# RF_Front.net
KiCad netlist of a schematic drawn in Altium Designer
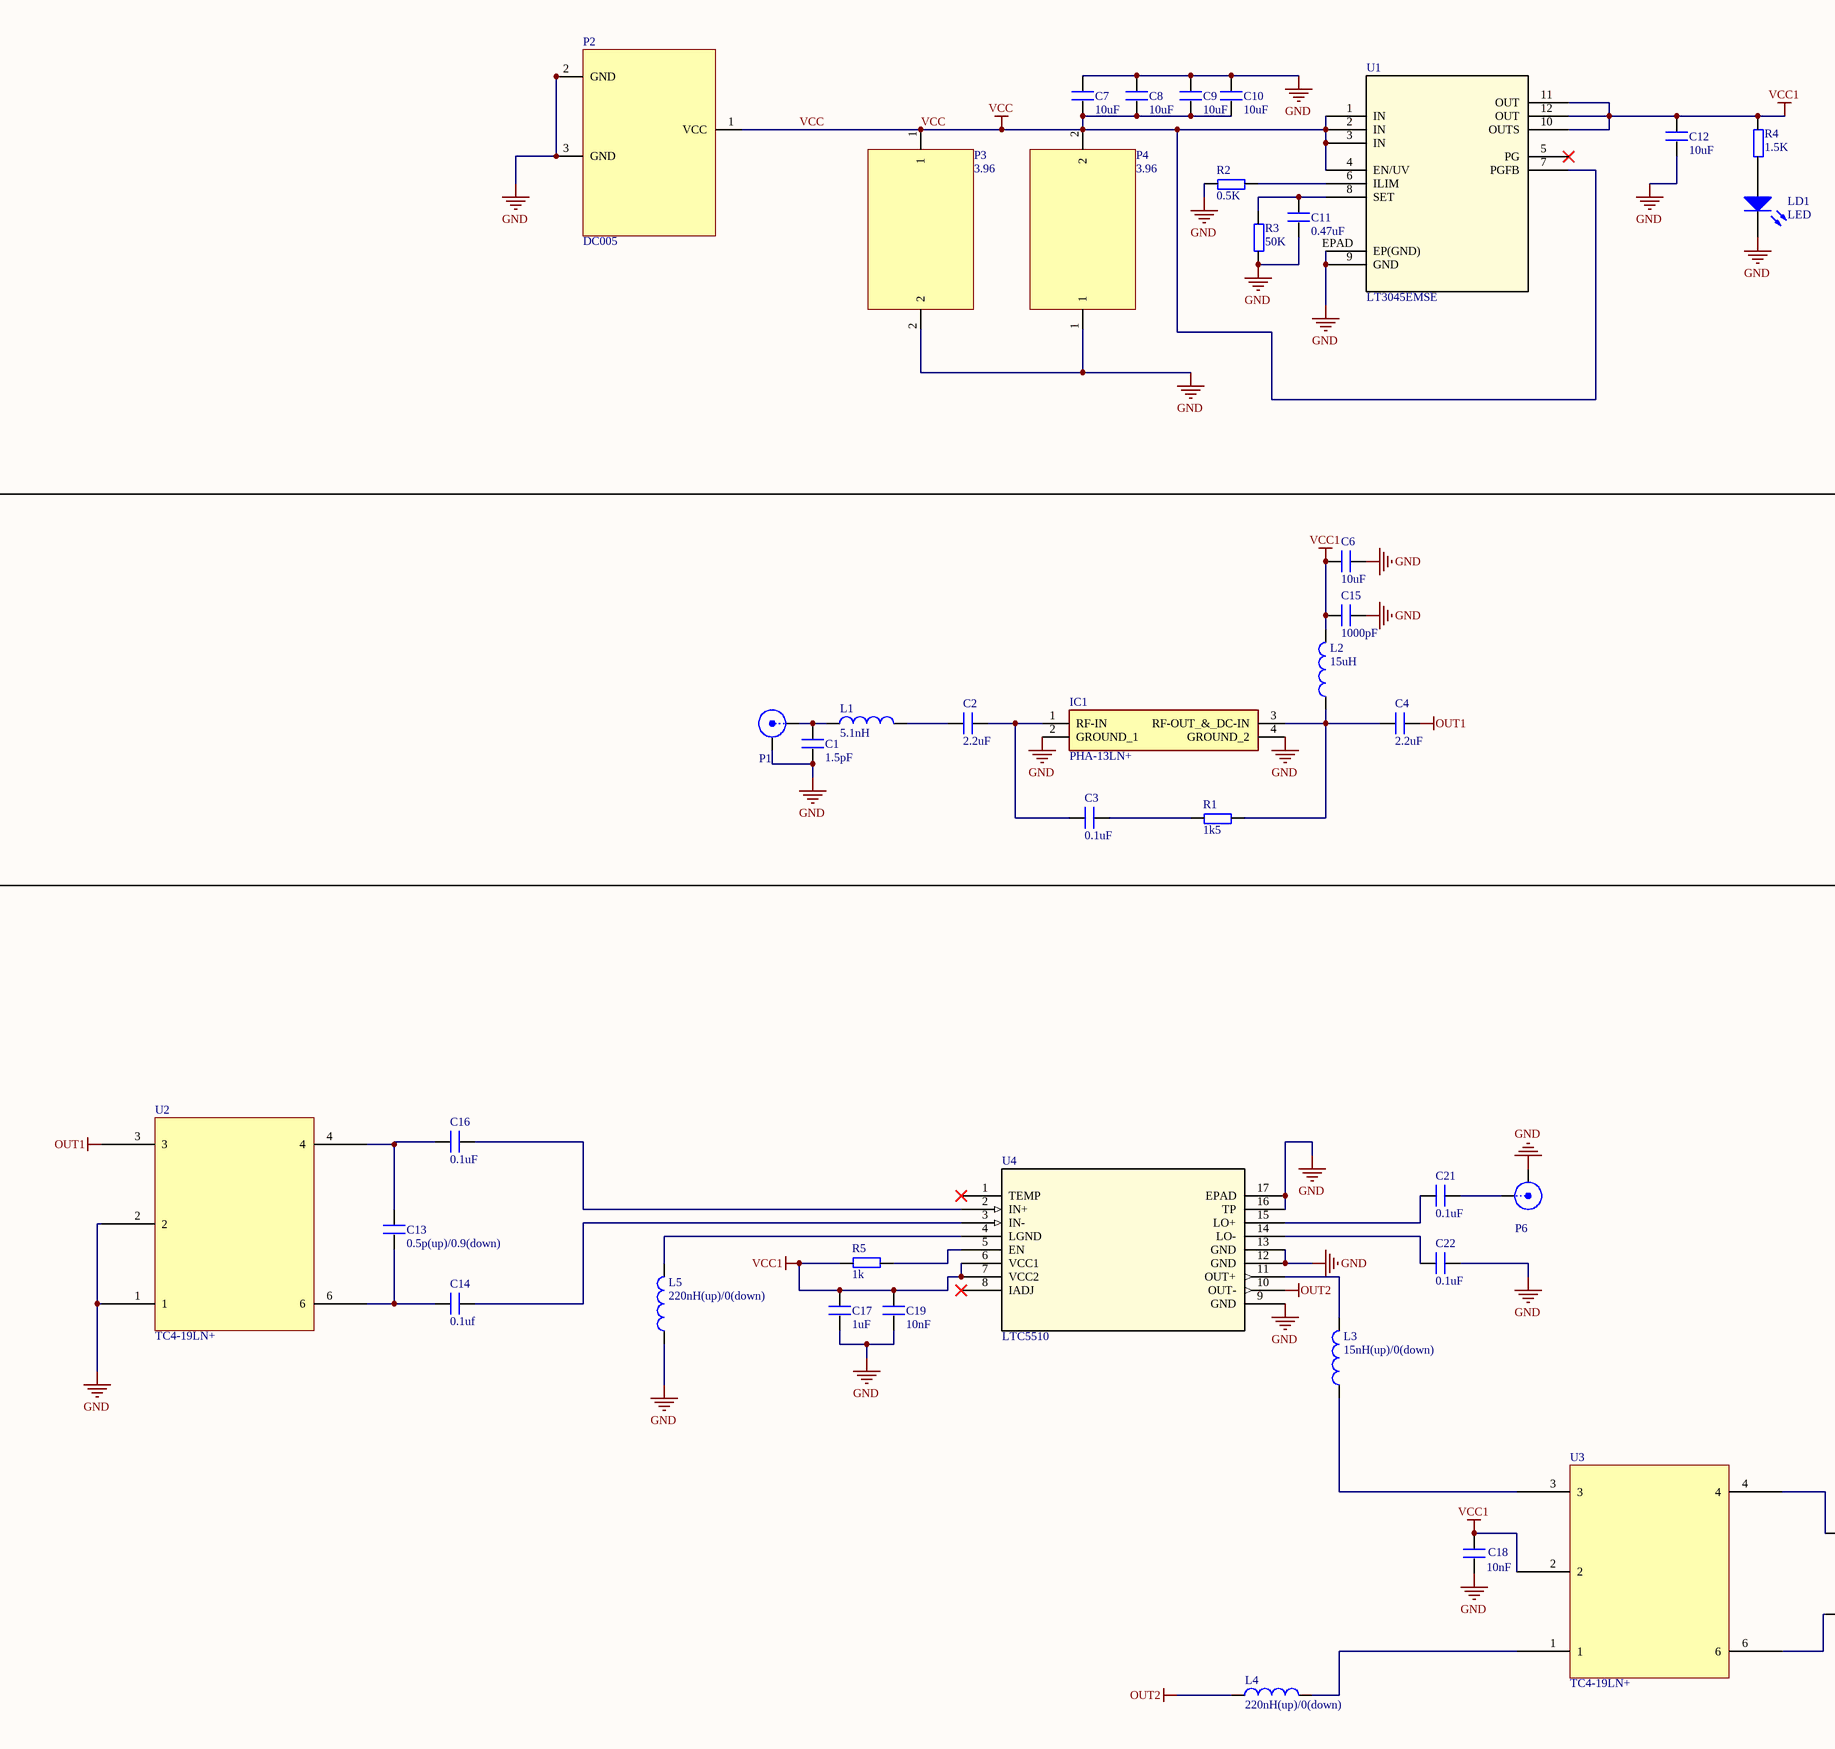
[diagram p0: RF Front.SchDoc, left]
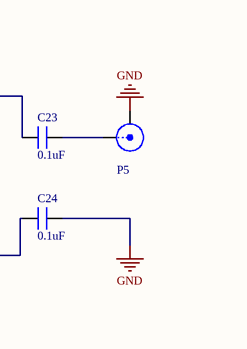
[diagram p1: RF Front.SchDoc, right]

(export (version "E")
  (design (tool "Eeschema 10.0.6"))
  (components
    (comp (ref "C1")
      (value "1.5pF")
      (footprint "0402")
      (description "Capacitor")
      (libsource (lib "MYLIB") (part "C"))
    )
    (comp (ref "C2")
      (value "2.2uF")
      (footprint "0402")
      (description "Capacitor")
      (libsource (lib "MYLIB") (part "C"))
    )
    (comp (ref "C3")
      (value "0.1uF")
      (footprint "0402")
      (description "Capacitor")
      (libsource (lib "MYLIB") (part "C"))
    )
    (comp (ref "C4")
      (value "2.2uF")
      (footprint "0402")
      (description "Capacitor")
      (libsource (lib "MYLIB") (part "C"))
    )
    (comp (ref "C6")
      (value "10uF")
      (footprint "0603C")
      (description "Capacitor")
      (libsource (lib "MYLIB") (part "C"))
    )
    (comp (ref "C7")
      (value "10uF")
      (footprint "CAP 1.5*4*8")
      (description "Capacitor")
      (libsource (lib "MYLIB") (part "C"))
    )
    (comp (ref "C8")
      (value "10uF")
      (footprint "CAP 1.5*4*8")
      (description "Capacitor")
      (libsource (lib "MYLIB") (part "C"))
    )
    (comp (ref "C9")
      (value "10uF")
      (footprint "0603C")
      (description "Capacitor")
      (libsource (lib "MYLIB") (part "C"))
    )
    (comp (ref "C10")
      (value "10uF")
      (footprint "0603C")
      (description "Capacitor")
      (libsource (lib "MYLIB") (part "C"))
    )
    (comp (ref "C11")
      (value "0.47uF")
      (footprint "0402")
      (description "Capacitor")
      (libsource (lib "MYLIB") (part "C"))
    )
    (comp (ref "C12")
      (value "10uF")
      (footprint "0402")
      (description "Capacitor")
      (libsource (lib "MYLIB") (part "C"))
    )
    (comp (ref "C13")
      (value "0.5p(up)/0.9(down)")
      (footprint "0402")
      (description "Capacitor")
      (libsource (lib "MYLIB") (part "C"))
    )
    (comp (ref "C14")
      (value "0.1uf")
      (footprint "0402")
      (description "Capacitor")
      (libsource (lib "MYLIB") (part "C"))
    )
    (comp (ref "C15")
      (value "1000pF")
      (footprint "0402")
      (description "Capacitor")
      (libsource (lib "MYLIB") (part "C"))
    )
    (comp (ref "C16")
      (value "0.1uF")
      (footprint "0402")
      (description "Capacitor")
      (libsource (lib "MYLIB") (part "C"))
    )
    (comp (ref "C17")
      (value "1uF")
      (footprint "0402")
      (description "Capacitor")
      (libsource (lib "MYLIB") (part "C"))
    )
    (comp (ref "C18")
      (value "10nF")
      (footprint "0402")
      (description "Capacitor")
      (libsource (lib "MYLIB") (part "C"))
    )
    (comp (ref "C19")
      (value "10nF")
      (footprint "0402")
      (description "Capacitor")
      (libsource (lib "MYLIB") (part "C"))
    )
    (comp (ref "C21")
      (value "0.1uF")
      (footprint "0402")
      (description "Capacitor")
      (libsource (lib "MYLIB") (part "C"))
    )
    (comp (ref "C22")
      (value "0.1uF")
      (footprint "0402")
      (description "Capacitor")
      (libsource (lib "MYLIB") (part "C"))
    )
    (comp (ref "C23")
      (value "0.1uF")
      (footprint "0402")
      (description "Capacitor")
      (libsource (lib "MYLIB") (part "C"))
    )
    (comp (ref "C24")
      (value "0.1uF")
      (footprint "0402")
      (description "Capacitor")
      (libsource (lib "MYLIB") (part "C"))
    )
    (comp (ref "IC1")
      (value "PHA-13LN+")
      (footprint "MYLIB:PHA13LN")
      (description "Integrated Circuit")
      (fields (field (name "MOUSER PART NUMBER") "139-PHA-13LN"))
      (libsource (lib "*") (part "PHA-13LN+"))
    )
    (comp (ref "L1")
      (value "5.1nH")
      (footprint "0402")
      (description "Inductor")
      (fields (field (name "PUBLISHER") "Altium Limited"))
      (libsource (lib "MYLIB") (part "Inductor"))
    )
    (comp (ref "L2")
      (value "15uH")
      (footprint "1206C")
      (description "Inductor")
      (fields (field (name "PUBLISHER") "Altium Limited"))
      (libsource (lib "MYLIB") (part "Inductor"))
    )
    (comp (ref "L3")
      (value "15nH(up)/0(down)")
      (footprint "0603L")
      (description "Inductor")
      (fields (field (name "PUBLISHER") "Altium Limited"))
      (libsource (lib "MYLIB") (part "Inductor"))
    )
    (comp (ref "L4")
      (value "220nH(up)/0(down)")
      (footprint "0603L")
      (description "Inductor")
      (fields (field (name "PUBLISHER") "Altium Limited"))
      (libsource (lib "MYLIB") (part "Inductor"))
    )
    (comp (ref "L5")
      (value "220nH(up)/0(down)")
      (footprint "0603L")
      (description "Inductor")
      (fields (field (name "PUBLISHER") "Altium Limited"))
      (libsource (lib "MYLIB") (part "Inductor"))
    )
    (comp (ref "LD1")
      (value "LED")
      (footprint "SMDLED")
      (description "Typical RED, GREEN, YELLOW, AMBER GaAs LED")
      (fields (field (name "PUBLISHER") "Altium Limited"))
      (libsource (lib "MYLIB") (part "LED"))
    )
    (comp (ref "P1")
      (value "SMA")
      (footprint "SMA")
      (description "SMA Connector")
      (libsource (lib "MYLIB") (part "SMA"))
    )
    (comp (ref "P2") (value "DC005") (footprint "DC10B") (libsource (lib "MYLIB") (part "DC005")))
    (comp (ref "P3") (value "3.96") (footprint "3.96") (libsource (lib "") (part "3.96_1")))
    (comp (ref "P4") (value "3.96") (footprint "3.96") (libsource (lib "MYLIB") (part "3.96")))
    (comp (ref "P5")
      (value "SMA")
      (footprint "SMA")
      (description "SMA Connector")
      (libsource (lib "MYLIB") (part "SMA"))
    )
    (comp (ref "P6")
      (value "SMA")
      (footprint "SMA")
      (description "SMA Connector")
      (libsource (lib "MYLIB") (part "SMA"))
    )
    (comp (ref "R1")
      (value "1k5")
      (footprint "0402")
      (description "Resistor")
      (libsource (lib "MYLIB") (part "Resistor"))
    )
    (comp (ref "R2")
      (value "0.5K")
      (footprint "0402")
      (description "Resistor")
      (libsource (lib "MYLIB") (part "Resistor"))
    )
    (comp (ref "R3")
      (value "50K")
      (footprint "0402")
      (description "Resistor")
      (libsource (lib "MYLIB") (part "Resistor"))
    )
    (comp (ref "R4")
      (value "1.5K")
      (footprint "0603R")
      (description "Resistor")
      (libsource (lib "MYLIB") (part "Resistor"))
    )
    (comp (ref "R5")
      (value "1k")
      (footprint "0603R")
      (description "Resistor")
      (libsource (lib "MYLIB") (part "Resistor"))
    )
    (comp (ref "U1")
      (value "LT3045EMSE")
      (footprint "MSOP12-MSE-RevG_ADI")
      (description "No Description Available")
      (fields (field (name "COPYRIGHT") "Copyright (C) 2018 Accelerated Designs. All rights reserved"))
      (libsource (lib "MYLIB") (part "LT3045EMSE"))
    )
    (comp (ref "U2") (value "TC4-19LN+") (footprint "AT224") (libsource (lib "MYLIB") (part "TC4-19LN+")))
    (comp (ref "U3") (value "TC4-19LN+") (footprint "AT224") (libsource (lib "MYLIB") (part "TC4-19LN+")))
    (comp (ref "U4")
      (value "LTC5510")
      (footprint "QFN-16_UF")
      (description "1MHz 至 6GHz、宽带、高线性度有源混频器")
      (fields
        (field (name "MANUFACTURER_PART_NUMBER") "LTC5510IUF#TRPBF")
        (field (name "COPYRIGHT") "Copyright (C) 2018 Accelerated Designs. All rights reserved")
      )
      (libsource (lib "MYLIB") (part "LTC5510"))
    )
  )
  (nets
    (net (code "1") (name "GND") (class "Default")
      (node (ref "C1") (pin "1") (pintype "passive"))
      (node (ref "C10") (pin "2") (pintype "passive"))
      (node (ref "C11") (pin "2") (pintype "passive"))
      (node (ref "C12") (pin "1") (pintype "passive"))
      (node (ref "C15") (pin "1") (pintype "passive"))
      (node (ref "C17") (pin "2") (pintype "passive"))
      (node (ref "C18") (pin "1") (pintype "passive"))
      (node (ref "C19") (pin "2") (pintype "passive"))
      (node (ref "C22") (pin "2") (pintype "passive"))
      (node (ref "C24") (pin "2") (pintype "passive"))
      (node (ref "C6") (pin "1") (pintype "passive"))
      (node (ref "C7") (pin "2") (pintype "passive"))
      (node (ref "C8") (pin "2") (pintype "passive"))
      (node (ref "C9") (pin "2") (pintype "passive"))
      (node (ref "IC1") (pin "2") (pinfunction "GROUND_1_2") (pintype "passive"))
      (node (ref "IC1") (pin "4") (pinfunction "GROUND_2_4") (pintype "passive"))
      (node (ref "L5") (pin "1") (pinfunction "1_1") (pintype "passive"))
      (node (ref "LD1") (pin "2") (pinfunction "K_2") (pintype "passive"))
      (node (ref "P1") (pin "2") (pinfunction "Y_2") (pintype "passive"))
      (node (ref "P2") (pin "2") (pinfunction "GND_2") (pintype "passive"))
      (node (ref "P2") (pin "3") (pinfunction "GND_3") (pintype "passive"))
      (node (ref "P3") (pin "2") (pinfunction "2_2") (pintype "passive"))
      (node (ref "P4") (pin "1") (pinfunction "1_1") (pintype "passive"))
      (node (ref "P5") (pin "2") (pinfunction "Y_2") (pintype "passive"))
      (node (ref "P6") (pin "2") (pinfunction "Y_2") (pintype "passive"))
      (node (ref "R2") (pin "1") (pintype "passive"))
      (node (ref "R3") (pin "1") (pintype "passive"))
      (node (ref "U1") (pin "9") (pinfunction "GND_9") (pintype "passive"))
      (node (ref "U1") (pin "EPAD") (pinfunction "EP(GND)_EPAD") (pintype "passive"))
      (node (ref "U2") (pin "1") (pinfunction "1_1") (pintype "passive"))
      (node (ref "U2") (pin "2") (pinfunction "2_2") (pintype "passive"))
      (node (ref "U4") (pin "12") (pinfunction "GND_12") (pintype "power_in"))
      (node (ref "U4") (pin "13") (pinfunction "GND_13") (pintype "power_in"))
      (node (ref "U4") (pin "16") (pinfunction "TP_16") (pintype "passive"))
      (node (ref "U4") (pin "17") (pinfunction "EPAD_17") (pintype "passive"))
      (node (ref "U4") (pin "9") (pinfunction "GND_9") (pintype "power_in"))
    )
    (net (code "2") (name "Net-(C2-Pad2)") (class "Default")
      (node (ref "C2") (pin "2") (pintype "passive"))
      (node (ref "L1") (pin "2") (pinfunction "2_2") (pintype "passive"))
    )
    (net (code "3") (name "Net-(C3-Pad1)") (class "Default")
      (node (ref "C3") (pin "1") (pintype "passive"))
      (node (ref "R1") (pin "1") (pintype "passive"))
    )
    (net (code "4") (name "Net-(C13-Pad1)") (class "Default")
      (node (ref "C13") (pin "1") (pintype "passive"))
      (node (ref "C14") (pin "2") (pintype "passive"))
      (node (ref "U2") (pin "6") (pinfunction "6_6") (pintype "passive"))
    )
    (net (code "5") (name "Net-(C13-Pad2)") (class "Default")
      (node (ref "C13") (pin "2") (pintype "passive"))
      (node (ref "C16") (pin "1") (pintype "passive"))
      (node (ref "U2") (pin "4") (pinfunction "4_4") (pintype "passive"))
    )
    (net (code "6") (name "Net-(C23-Pad1)") (class "Default")
      (node (ref "C23") (pin "1") (pintype "passive"))
      (node (ref "U3") (pin "4") (pinfunction "4_4") (pintype "passive"))
    )
    (net (code "7") (name "Net-(C24-Pad1)") (class "Default")
      (node (ref "C24") (pin "1") (pintype "passive"))
      (node (ref "U3") (pin "6") (pinfunction "6_6") (pintype "passive"))
    )
    (net (code "8") (name "Net-(IC1-RF-IN)") (class "Default")
      (node (ref "C2") (pin "1") (pintype "passive"))
      (node (ref "C3") (pin "2") (pintype "passive"))
      (node (ref "IC1") (pin "1") (pinfunction "RF-IN_1") (pintype "passive"))
    )
    (net (code "9") (name "Net-(IC1-RF-OUT_&_DC-IN)") (class "Default")
      (node (ref "C4") (pin "2") (pintype "passive"))
      (node (ref "IC1") (pin "3") (pinfunction "RF-OUT_&_DC-IN_3") (pintype "passive"))
      (node (ref "L2") (pin "1") (pinfunction "1_1") (pintype "passive"))
      (node (ref "R1") (pin "2") (pintype "passive"))
    )
    (net (code "10") (name "Net-(L3-Pad1)") (class "Default")
      (node (ref "L3") (pin "1") (pinfunction "1_1") (pintype "passive"))
      (node (ref "U3") (pin "3") (pinfunction "3_3") (pintype "passive"))
    )
    (net (code "11") (name "Net-(L4-Pad2)") (class "Default")
      (node (ref "L4") (pin "2") (pinfunction "2_2") (pintype "passive"))
      (node (ref "U3") (pin "1") (pinfunction "1_1") (pintype "passive"))
    )
    (net (code "12") (name "Net-(LD1-A)") (class "Default")
      (node (ref "LD1") (pin "1") (pinfunction "A_1") (pintype "passive"))
      (node (ref "R4") (pin "1") (pintype "passive"))
    )
    (net (code "13") (name "Net-(P1-X)") (class "Default")
      (node (ref "C1") (pin "2") (pintype "passive"))
      (node (ref "L1") (pin "1") (pinfunction "1_1") (pintype "passive"))
      (node (ref "P1") (pin "1") (pinfunction "X_1") (pintype "passive"))
    )
    (net (code "14") (name "Net-(P5-X)") (class "Default")
      (node (ref "C23") (pin "2") (pintype "passive"))
      (node (ref "P5") (pin "1") (pinfunction "X_1") (pintype "passive"))
    )
    (net (code "15") (name "Net-(P6-X)") (class "Default")
      (node (ref "C21") (pin "1") (pintype "passive"))
      (node (ref "P6") (pin "1") (pinfunction "X_1") (pintype "passive"))
    )
    (net (code "16") (name "Net-(U1-ILIM)") (class "Default")
      (node (ref "R2") (pin "2") (pintype "passive"))
      (node (ref "U1") (pin "6") (pinfunction "ILIM_6") (pintype "passive"))
    )
    (net (code "17") (name "Net-(U1-SET)") (class "Default")
      (node (ref "C11") (pin "1") (pintype "passive"))
      (node (ref "R3") (pin "2") (pintype "passive"))
      (node (ref "U1") (pin "8") (pinfunction "SET_8") (pintype "passive"))
    )
    (net (code "18") (name "Net-(U4-EN)") (class "Default")
      (node (ref "R5") (pin "1") (pintype "passive"))
      (node (ref "U4") (pin "5") (pinfunction "EN_5") (pintype "passive"))
    )
    (net (code "19") (name "Net-(U4-IN+)") (class "Default")
      (node (ref "C16") (pin "2") (pintype "passive"))
      (node (ref "U4") (pin "2") (pinfunction "IN+_2") (pintype "input"))
    )
    (net (code "20") (name "Net-(U4-IN-)") (class "Default")
      (node (ref "C14") (pin "1") (pintype "passive"))
      (node (ref "U4") (pin "3") (pinfunction "IN-_3") (pintype "input"))
    )
    (net (code "21") (name "Net-(U4-LGND)") (class "Default")
      (node (ref "L5") (pin "2") (pinfunction "2_2") (pintype "passive"))
      (node (ref "U4") (pin "4") (pinfunction "LGND_4") (pintype "power_in"))
    )
    (net (code "22") (name "Net-(U4-LO+)") (class "Default")
      (node (ref "C21") (pin "2") (pintype "passive"))
      (node (ref "U4") (pin "15") (pinfunction "LO+_15") (pintype "passive"))
    )
    (net (code "23") (name "Net-(U4-LO-)") (class "Default")
      (node (ref "C22") (pin "1") (pintype "passive"))
      (node (ref "U4") (pin "14") (pinfunction "LO-_14") (pintype "passive"))
    )
    (net (code "24") (name "Net-(U4-OUT+)") (class "Default")
      (node (ref "L3") (pin "2") (pinfunction "2_2") (pintype "passive"))
      (node (ref "U4") (pin "11") (pinfunction "OUT+_11") (pintype "output"))
    )
    (net (code "25") (name "OUT1") (class "Default")
      (node (ref "C4") (pin "1") (pintype "passive"))
      (node (ref "U2") (pin "3") (pinfunction "3_3") (pintype "passive"))
    )
    (net (code "26") (name "OUT2") (class "Default")
      (node (ref "L4") (pin "1") (pinfunction "1_1") (pintype "passive"))
      (node (ref "U4") (pin "10") (pinfunction "OUT-_10") (pintype "output"))
    )
    (net (code "27") (name "VCC") (class "Default")
      (node (ref "C10") (pin "1") (pintype "passive"))
      (node (ref "C7") (pin "1") (pintype "passive"))
      (node (ref "C8") (pin "1") (pintype "passive"))
      (node (ref "C9") (pin "1") (pintype "passive"))
      (node (ref "P2") (pin "1") (pinfunction "VCC_1") (pintype "passive"))
      (node (ref "P3") (pin "1") (pinfunction "1_1") (pintype "passive"))
      (node (ref "P4") (pin "2") (pinfunction "2_2") (pintype "passive"))
      (node (ref "U1") (pin "1") (pinfunction "IN_1") (pintype "passive"))
      (node (ref "U1") (pin "2") (pinfunction "IN_2") (pintype "passive"))
      (node (ref "U1") (pin "3") (pinfunction "IN_3") (pintype "passive"))
      (node (ref "U1") (pin "4") (pinfunction "EN/UV_4") (pintype "passive"))
      (node (ref "U1") (pin "7") (pinfunction "PGFB_7") (pintype "passive"))
    )
    (net (code "28") (name "VCC1") (class "Default")
      (node (ref "C12") (pin "2") (pintype "passive"))
      (node (ref "C15") (pin "2") (pintype "passive"))
      (node (ref "C17") (pin "1") (pintype "passive"))
      (node (ref "C18") (pin "2") (pintype "passive"))
      (node (ref "C19") (pin "1") (pintype "passive"))
      (node (ref "C6") (pin "2") (pintype "passive"))
      (node (ref "L2") (pin "2") (pinfunction "2_2") (pintype "passive"))
      (node (ref "R4") (pin "2") (pintype "passive"))
      (node (ref "R5") (pin "2") (pintype "passive"))
      (node (ref "U1") (pin "10") (pinfunction "OUTS_10") (pintype "passive"))
      (node (ref "U1") (pin "11") (pinfunction "OUT_11") (pintype "passive"))
      (node (ref "U1") (pin "12") (pinfunction "OUT_12") (pintype "passive"))
      (node (ref "U3") (pin "2") (pinfunction "2_2") (pintype "passive"))
      (node (ref "U4") (pin "6") (pinfunction "VCC1_6") (pintype "power_in"))
      (node (ref "U4") (pin "7") (pinfunction "VCC2_7") (pintype "power_in"))
    )
    (net (code "29") (name "unconnected-(U1-PG-Pad5)") (class "Default")
      (node (ref "U1") (pin "5") (pinfunction "PG_5") (pintype "passive+no_connect"))
    )
    (net (code "30") (name "unconnected-(U4-IADJ-Pad8)") (class "Default")
      (node (ref "U4") (pin "8") (pinfunction "IADJ_8") (pintype "passive+no_connect"))
    )
    (net (code "31") (name "unconnected-(U4-TEMP-Pad1)") (class "Default")
      (node (ref "U4") (pin "1") (pinfunction "TEMP_1") (pintype "passive+no_connect"))
    )
  )
)
